# 3_3VBuck_MP2315S_P1.net
KiCad netlist of a schematic drawn in EasyEDA Pro
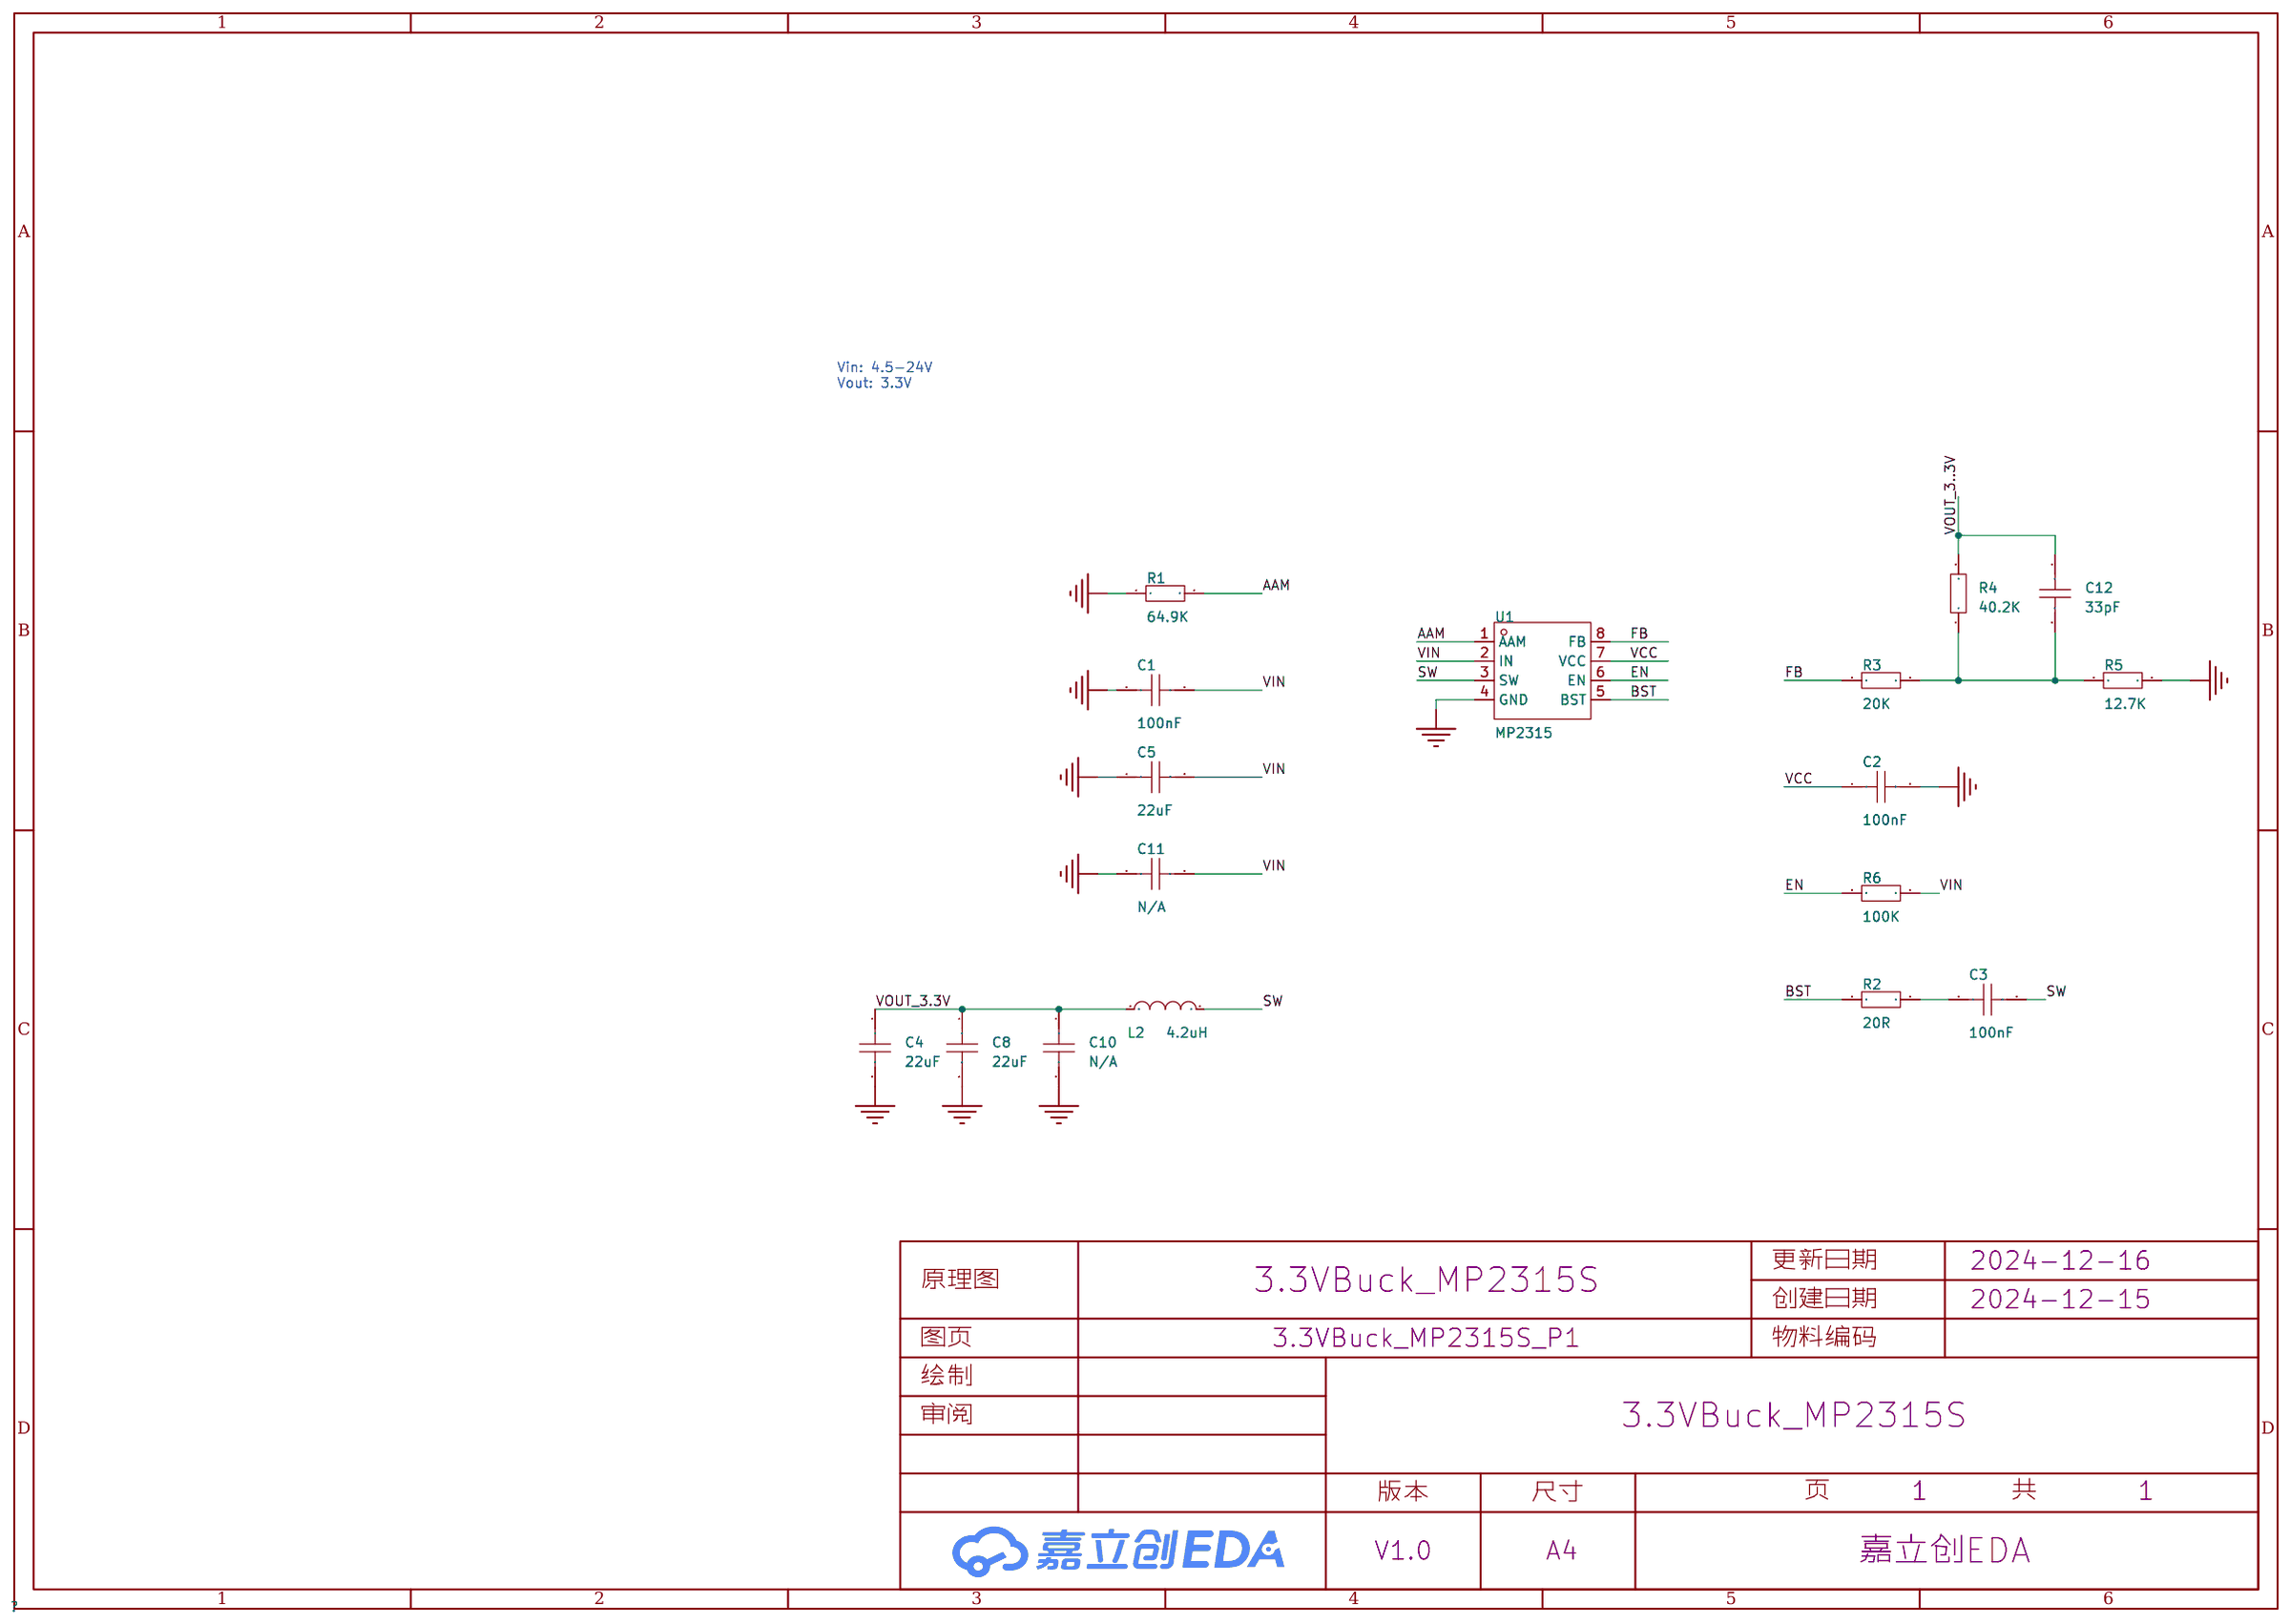
[diagram p0: schematic sheet]

(export (version "E")
  (design (tool "Eeschema 10.0.6"))
  (components
    (comp (ref "C1")
      (value "100nF")
      (footprint "easyedapro:C0805")
      (libsource (lib "easyedapro") (part "CapAcitance"))
    )
    (comp (ref "C2")
      (value "100nF")
      (footprint "easyedapro:C0805")
      (libsource (lib "easyedapro") (part "CapAcitance"))
    )
    (comp (ref "C3")
      (value "100nF")
      (footprint "easyedapro:C0805")
      (libsource (lib "easyedapro") (part "CapAcitance"))
    )
    (comp (ref "C4")
      (value "22uF")
      (footprint "easyedapro:C0805")
      (libsource (lib "easyedapro") (part "CapAcitance"))
    )
    (comp (ref "C5")
      (value "22uF")
      (footprint "easyedapro:C0805")
      (libsource (lib "easyedapro") (part "CapAcitance"))
    )
    (comp (ref "C8")
      (value "100nF")
      (footprint "easyedapro:C0805")
      (libsource (lib "easyedapro") (part "CapAcitance"))
    )
    (comp (ref "C10")
      (value "N/A")
      (footprint "easyedapro:C0805")
      (libsource (lib "easyedapro") (part "CapAcitance"))
    )
    (comp (ref "C11")
      (value "100nF")
      (footprint "easyedapro:C0805")
      (libsource (lib "easyedapro") (part "CapAcitance"))
    )
    (comp (ref "C12")
      (value "33pF")
      (footprint "easyedapro:C0805")
      (libsource (lib "easyedapro") (part "CapAcitance"))
    )
    (comp (ref "L2")
      (value "4.2uH")
      (footprint "easyedapro:IND-SMD_L7.1-W6.6_MJC-0603T")
      (description "电感值:5.6uH;精度:±20%;额定电流:5.5A;饱和电流(Isat):7A;类型:一体成型电感;")
      (fields
        (field (name "Manufacturer Part") "CXP0630-5R6M-AG(5.6uh)")
        (field (name "Manufacturer") "DMBJ(振宝佳)")
      )
      (libsource (lib "easyedapro") (part "CXP0630-5R6M-AG(5.6UH)"))
    )
    (comp (ref "R1")
      (value "64.9K")
      (footprint "easyedapro:R0805")
      (libsource (lib "easyedapro") (part "电阻"))
    )
    (comp (ref "R2") (value "20R") (footprint "easyedapro:R0805") (libsource (lib "easyedapro") (part "电阻")))
    (comp (ref "R3") (value "20K") (footprint "easyedapro:R0805") (libsource (lib "easyedapro") (part "电阻")))
    (comp (ref "R4")
      (value "40.2K")
      (footprint "easyedapro:R0805")
      (libsource (lib "easyedapro") (part "电阻"))
    )
    (comp (ref "R5")
      (value "12.7K")
      (footprint "easyedapro:R0805")
      (libsource (lib "easyedapro") (part "电阻"))
    )
    (comp (ref "R6") (value "100K") (footprint "easyedapro:R0805") (libsource (lib "easyedapro") (part "电阻")))
    (comp (ref "U1")
      (value "MP2315")
      (footprint "easyedapro:SOT-23-8_L2.9-W1.6-P0.65-LS2.8-BL")
      (libsource (lib "easyedapro") (part "MP2315"))
    )
  )
  (nets
    (net (code "1") (name "/AAM") (class "Default")
      (node (ref "R1") (pin "2") (pinfunction "2_2") (pintype "input"))
      (node (ref "U1") (pin "1") (pinfunction "AAM_1") (pintype "unspecified"))
    )
    (net (code "2") (name "/BST") (class "Default")
      (node (ref "R2") (pin "1") (pinfunction "1_1") (pintype "input"))
      (node (ref "U1") (pin "5") (pinfunction "BST_5") (pintype "unspecified"))
    )
    (net (code "3") (name "/EN") (class "Default")
      (node (ref "R6") (pin "2") (pinfunction "2_2") (pintype "input"))
      (node (ref "U1") (pin "6") (pinfunction "EN_6") (pintype "unspecified"))
    )
    (net (code "4") (name "/FB") (class "Default")
      (node (ref "R3") (pin "1") (pinfunction "1_1") (pintype "input"))
      (node (ref "U1") (pin "8") (pinfunction "FB_8") (pintype "unspecified"))
    )
    (net (code "5") (name "/SW") (class "Default")
      (node (ref "C3") (pin "2") (pinfunction "2_2") (pintype "input"))
      (node (ref "L2") (pin "2") (pinfunction "2_2") (pintype "unspecified"))
      (node (ref "U1") (pin "3") (pinfunction "SW_3") (pintype "unspecified"))
    )
    (net (code "6") (name "/VCC") (class "Default")
      (node (ref "C2") (pin "1") (pinfunction "1_1") (pintype "input"))
      (node (ref "U1") (pin "7") (pinfunction "VCC_7") (pintype "unspecified"))
    )
    (net (code "7") (name "/VIN") (class "Default")
      (node (ref "C1") (pin "2") (pinfunction "2_2") (pintype "input"))
      (node (ref "C11") (pin "2") (pinfunction "2_2") (pintype "input"))
      (node (ref "C5") (pin "2") (pinfunction "2_2") (pintype "input"))
      (node (ref "R6") (pin "1") (pinfunction "1_1") (pintype "input"))
      (node (ref "U1") (pin "2") (pinfunction "IN_2") (pintype "unspecified"))
    )
    (net (code "8") (name "/VOUT_3..3V") (class "Default")
      (node (ref "C12") (pin "1") (pinfunction "1_1") (pintype "input"))
      (node (ref "R4") (pin "2") (pinfunction "2_2") (pintype "input"))
    )
    (net (code "9") (name "/VOUT_3.3V") (class "Default")
      (node (ref "C10") (pin "1") (pinfunction "1_1") (pintype "input"))
      (node (ref "C4") (pin "1") (pinfunction "1_1") (pintype "input"))
      (node (ref "C8") (pin "1") (pinfunction "1_1") (pintype "input"))
      (node (ref "L2") (pin "1") (pinfunction "1_1") (pintype "unspecified"))
    )
    (net (code "10") (name "GND") (class "Default")
      (node (ref "C1") (pin "1") (pinfunction "1_1") (pintype "input"))
      (node (ref "C10") (pin "2") (pinfunction "2_2") (pintype "input"))
      (node (ref "C11") (pin "1") (pinfunction "1_1") (pintype "input"))
      (node (ref "C2") (pin "2") (pinfunction "2_2") (pintype "input"))
      (node (ref "C4") (pin "2") (pinfunction "2_2") (pintype "input"))
      (node (ref "C5") (pin "1") (pinfunction "1_1") (pintype "input"))
      (node (ref "C8") (pin "2") (pinfunction "2_2") (pintype "input"))
      (node (ref "R1") (pin "1") (pinfunction "1_1") (pintype "input"))
      (node (ref "R5") (pin "2") (pinfunction "2_2") (pintype "input"))
      (node (ref "U1") (pin "4") (pinfunction "GND_4") (pintype "unspecified"))
    )
    (net (code "11") (name "Net-(C3-Pad1)") (class "Default")
      (node (ref "C3") (pin "1") (pinfunction "1_1") (pintype "input"))
      (node (ref "R2") (pin "2") (pinfunction "2_2") (pintype "input"))
    )
    (net (code "12") (name "Net-(C12-Pad2)") (class "Default")
      (node (ref "C12") (pin "2") (pinfunction "2_2") (pintype "input"))
      (node (ref "R3") (pin "2") (pinfunction "2_2") (pintype "input"))
      (node (ref "R4") (pin "1") (pinfunction "1_1") (pintype "input"))
      (node (ref "R5") (pin "1") (pinfunction "1_1") (pintype "input"))
    )
  )
)
